# retro.net
KiCad netlist of a schematic drawn in Altium Designer
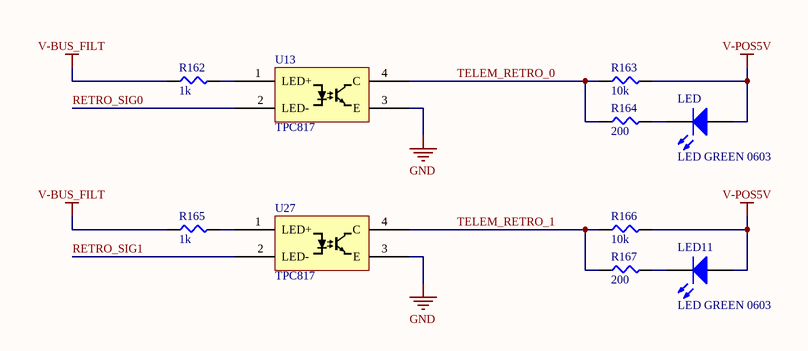
[diagram p0: retro.SchDoc]

(export (version "E")
  (design (tool "Eeschema 10.0.6"))
  (components
    (comp (ref "LED")
      (value "LED GREEN 0603")
      (footprint "LED 0603 GREEN")
      (fields (field (name "MANUFACTURER") "Lite-On Inc."))
      (libsource (lib "misc") (part "LED GREEN 0603"))
    )
    (comp (ref "LED11")
      (value "LED GREEN 0603")
      (footprint "LED 0603 GREEN")
      (fields (field (name "MANUFACTURER") "Lite-On Inc."))
      (libsource (lib "misc") (part "LED GREEN 0603"))
    )
    (comp (ref "R162")
      (value "1k")
      (footprint "SMD-0805-RES")
      (description "RES SMD 1K OHM 5% 1/2W 0805")
      (fields
        (field (name "PART NUMBER") "ERJ-P06J102V")
        (field (name "DIGI-KEY PART NUMBER") "P1.0KADCT-ND")
      )
      (libsource (lib "resistors") (part "ERJ-P06J102V"))
    )
    (comp (ref "R163")
      (value "10k")
      (footprint "SMD-0805-RES")
      (description "RES SMD 10K OHM 5% 1/2W 0805")
      (fields (field (name "PART NUMBER") "ERJ-P06J103V") (field (name "DIGI-KEY PART NUMBER") "P10KADCT-ND"))
      (libsource (lib "resistors") (part "ERJ-P06J103V"))
    )
    (comp (ref "R164")
      (value "200")
      (footprint "SMD-0805-RES")
      (description "RES SMD 200 OHM 1% 1/8W 0805")
      (fields (field (name "PART NUMBER") "ERJ-6ENF2000V") (field (name "DIGI-KEY PART NUMBER") "P200CCT-ND"))
      (libsource (lib "resistors") (part "ERJ-6ENF2000V"))
    )
    (comp (ref "R165")
      (value "1k")
      (footprint "SMD-0805-RES")
      (description "RES SMD 1K OHM 5% 1/2W 0805")
      (fields
        (field (name "PART NUMBER") "ERJ-P06J102V")
        (field (name "DIGI-KEY PART NUMBER") "P1.0KADCT-ND")
      )
      (libsource (lib "resistors") (part "ERJ-P06J102V"))
    )
    (comp (ref "R166")
      (value "10k")
      (footprint "SMD-0805-RES")
      (description "RES SMD 10K OHM 5% 1/2W 0805")
      (fields (field (name "PART NUMBER") "ERJ-P06J103V") (field (name "DIGI-KEY PART NUMBER") "P10KADCT-ND"))
      (libsource (lib "resistors") (part "ERJ-P06J103V"))
    )
    (comp (ref "R167")
      (value "200")
      (footprint "SMD-0805-RES")
      (description "RES SMD 200 OHM 1% 1/8W 0805")
      (fields (field (name "PART NUMBER") "ERJ-6ENF2000V") (field (name "DIGI-KEY PART NUMBER") "P200CCT-ND"))
      (libsource (lib "resistors") (part "ERJ-6ENF2000V"))
    )
    (comp (ref "U13")
      (value "TPC817")
      (footprint "SOT200P1005X328-5N")
      (description "OPTOISO 5KV TRANS 4SOP")
      (fields (field (name "MANUFACTURER") "Taiwan Semi"))
      (libsource (lib "ic") (part "TPC817"))
    )
    (comp (ref "U27")
      (value "TPC817")
      (footprint "SOT200P1005X328-5N")
      (description "OPTOISO 5KV TRANS 4SOP")
      (fields (field (name "MANUFACTURER") "Taiwan Semi"))
      (libsource (lib "ic") (part "TPC817"))
    )
  )
  (nets
    (net (code "1") (name "/RETRO_SIG0") (class "Default")
      (node (ref "U13") (pin "2") (pinfunction "LED-_2") (pintype "passive"))
    )
    (net (code "2") (name "/RETRO_SIG1") (class "Default")
      (node (ref "U27") (pin "2") (pinfunction "LED-_2") (pintype "passive"))
    )
    (net (code "3") (name "/TELEM_RETRO_0") (class "Default")
      (node (ref "R163") (pin "1") (pinfunction "1_1") (pintype "passive"))
      (node (ref "R164") (pin "1") (pinfunction "1_1") (pintype "passive"))
      (node (ref "U13") (pin "4") (pinfunction "C_4") (pintype "passive"))
    )
    (net (code "4") (name "/TELEM_RETRO_1") (class "Default")
      (node (ref "R166") (pin "1") (pinfunction "1_1") (pintype "passive"))
      (node (ref "R167") (pin "1") (pinfunction "1_1") (pintype "passive"))
      (node (ref "U27") (pin "4") (pinfunction "C_4") (pintype "passive"))
    )
    (net (code "5") (name "GND") (class "Default")
      (node (ref "U13") (pin "3") (pinfunction "E_3") (pintype "passive"))
      (node (ref "U27") (pin "3") (pinfunction "E_3") (pintype "passive"))
    )
    (net (code "6") (name "Net-(LED-K)") (class "Default")
      (node (ref "LED") (pin "2") (pinfunction "K_2") (pintype "passive"))
      (node (ref "R164") (pin "2") (pinfunction "2_2") (pintype "passive"))
    )
    (net (code "7") (name "Net-(LED11-K)") (class "Default")
      (node (ref "LED11") (pin "2") (pinfunction "K_2") (pintype "passive"))
      (node (ref "R167") (pin "2") (pinfunction "2_2") (pintype "passive"))
    )
    (net (code "8") (name "Net-(U13-LED+)") (class "Default")
      (node (ref "R162") (pin "2") (pinfunction "2_2") (pintype "passive"))
      (node (ref "U13") (pin "1") (pinfunction "LED+_1") (pintype "passive"))
    )
    (net (code "9") (name "Net-(U27-LED+)") (class "Default")
      (node (ref "R165") (pin "2") (pinfunction "2_2") (pintype "passive"))
      (node (ref "U27") (pin "1") (pinfunction "LED+_1") (pintype "passive"))
    )
    (net (code "10") (name "V-BUS_FILT") (class "Default")
      (node (ref "R162") (pin "1") (pinfunction "1_1") (pintype "passive"))
      (node (ref "R165") (pin "1") (pinfunction "1_1") (pintype "passive"))
    )
    (net (code "11") (name "V-POS5V") (class "Default")
      (node (ref "LED") (pin "1") (pinfunction "A_1") (pintype "passive"))
      (node (ref "LED11") (pin "1") (pinfunction "A_1") (pintype "passive"))
      (node (ref "R163") (pin "2") (pinfunction "2_2") (pintype "passive"))
      (node (ref "R166") (pin "2") (pinfunction "2_2") (pintype "passive"))
    )
  )
)
